# Battery_power.net
KiCad netlist of a schematic drawn in Altium Designer
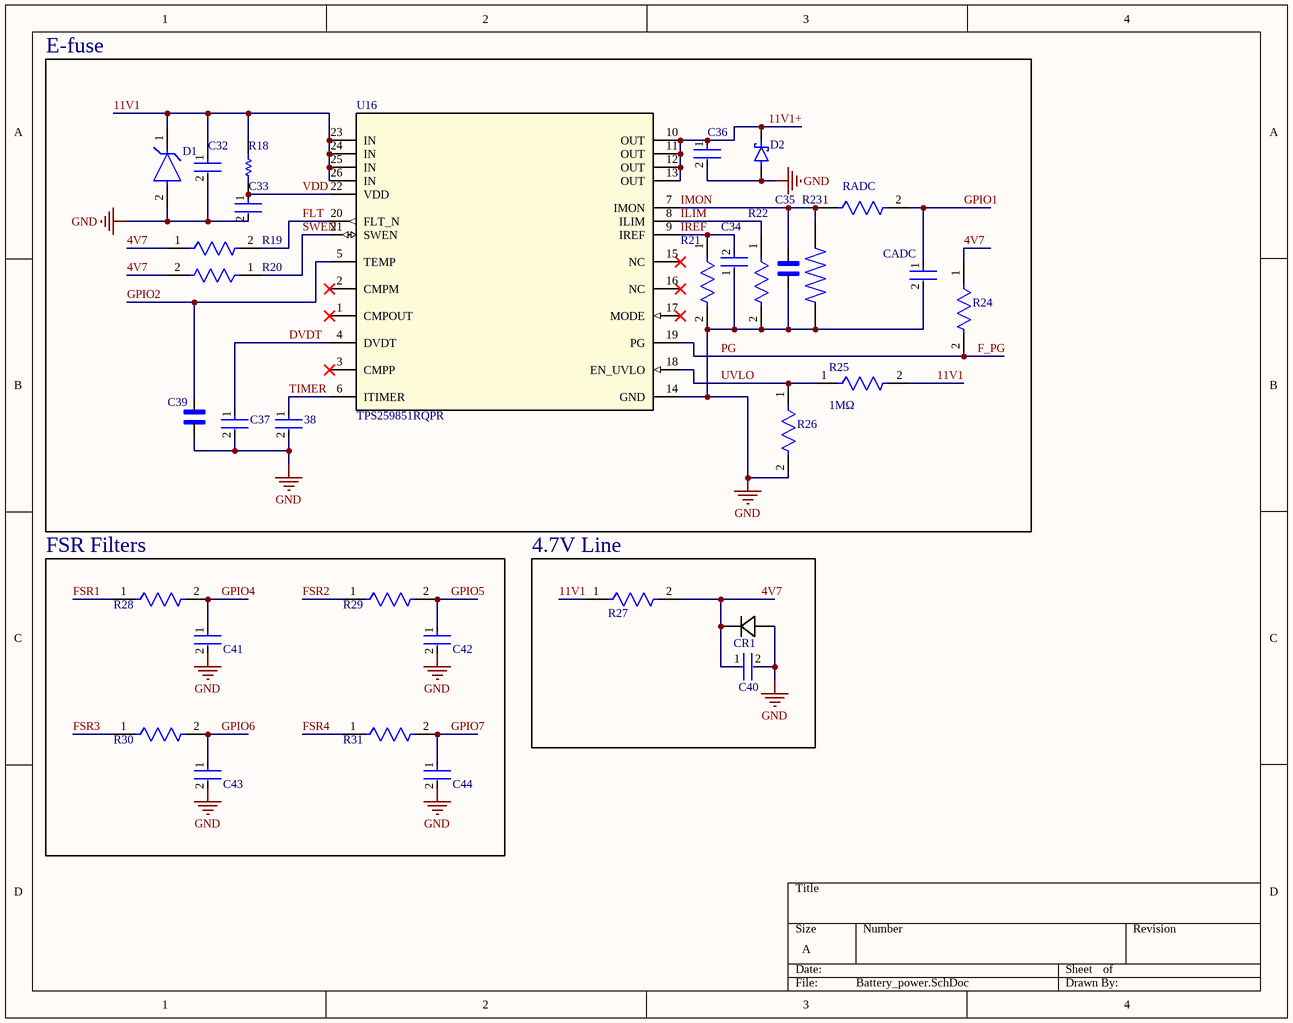
[diagram p0: Battery_power.SchDoc]

(export (version "E")
  (design (tool "Eeschema 10.0.6"))
  (components
    (comp (ref "38")
      (value "GRM155R71H104KE14D")
      (footprint "FP-GRM155-0_05-IPC_B")
      (description "Chip Multilayer Ceramic Capacitors for General Purpose, 0402, 0.10uF, X7R, 15%, 10%, 50V")
      (fields (field (name "VOLTAGE") "50V") (field (name "TOLERANCE") "10%"))
      (libsource (lib "Altium Content Vault") (part "02cd4be3c70576c341d710602a673aa"))
    )
    (comp (ref "C32")
      (value "CC0805KRX7R9BB104")
      (footprint "FP-CC0805-0_85-MFG")
      (description "CAP CER 0.1UF 50V X7R 0805")
      (fields (field (name "TOLERANCE") "0.1") (field (name "MANUFACTURER") "Yageo"))
      (libsource (lib "Altium Content Vault") (part "11868f565c42a9108669ba33697ecf6"))
    )
    (comp (ref "C33")
      (value "CC0805KKX7R9BB225")
      (footprint "FP-CC0805-0_85-MFG")
      (description "CAP CER 2.2UF 50V X7R 0805")
      (fields
        (field (name "OCTOPART") "https://octopart.com/cc0805kkx7r9bb225-yageo-51849248")
        (field (name "TOLERANCE") "0.1")
      )
      (libsource (lib "Altium Content Vault") (part "11868f565c42a9108669ba33697ecf6"))
    )
    (comp (ref "C34")
      (value "C1608C0G1E472J080AA")
      (footprint "FP-C1608-080-0_1-IPC_A")
      (description "Multilayer Ceramic Capacitors 4.7nF ±5% 25V C0G SMD 0603")
      (fields (field (name "TOLERANCE") "5%"))
      (libsource (lib "Altium Content Vault") (part "236180d848d6139a670b325ea6854c9"))
    )
    (comp (ref "C35")
      (value "GRM1885C1H101JA01D")
      (footprint "CAPC1608X90N")
      (description "SMD Capacitor C0G(EIA) with Capacitance: 100pF Tol. 5%. Rated Voltage: 50Vdc")
      (fields (field (name "MF") "Murata Electronics"))
      (libsource (lib "Bryan Heddle") (part "GRM1885C1H101JA01D"))
    )
    (comp (ref "C36")
      (value "CC0805KKX7R9BB225")
      (footprint "FP-CC0805-0_85-MFG")
      (description "CAP CER 2.2UF 50V X7R 0805")
      (fields
        (field (name "OCTOPART") "https://octopart.com/cc0805kkx7r9bb225-yageo-51849248")
        (field (name "TOLERANCE") "0.1")
      )
      (libsource (lib "Altium Content Vault") (part "11868f565c42a9108669ba33697ecf6"))
    )
    (comp (ref "C37")
      (value "GRM155R71H104KE14D")
      (footprint "FP-GRM155-0_05-IPC_B")
      (description "Chip Multilayer Ceramic Capacitors for General Purpose, 0402, 0.10uF, X7R, 15%, 10%, 50V")
      (fields (field (name "VOLTAGE") "50V") (field (name "TOLERANCE") "10%"))
      (libsource (lib "Altium Content Vault") (part "02cd4be3c70576c341d710602a673aa"))
    )
    (comp (ref "C39")
      (value "GRM1885C1H101JA01D")
      (footprint "CAPC1608X90N")
      (description "SMD Capacitor C0G(EIA) with Capacitance: 100pF Tol. 5%. Rated Voltage: 50Vdc")
      (fields (field (name "MF") "Murata Electronics"))
      (libsource (lib "Bryan Heddle") (part "GRM1885C1H101JA01D"))
    )
    (comp (ref "C40")
      (value "GRM155R71H104KE14D")
      (footprint "FP-GRM155-0_05-IPC_B")
      (description "Chip Multilayer Ceramic Capacitors for General Purpose, 0402, 0.10uF, X7R, 15%, 10%, 50V")
      (fields (field (name "VOLTAGE") "50V") (field (name "TOLERANCE") "10%"))
      (libsource (lib "Altium Content Vault") (part "02cd4be3c70576c341d710602a673aa"))
    )
    (comp (ref "C41")
      (value "GRM155R71H104KE14D")
      (footprint "FP-GRM155-0_05-IPC_B")
      (description "Chip Multilayer Ceramic Capacitors for General Purpose, 0402, 0.10uF, X7R, 15%, 10%, 50V")
      (fields (field (name "VOLTAGE") "50V") (field (name "TOLERANCE") "10%"))
      (libsource (lib "Altium Content Vault") (part "02cd4be3c70576c341d710602a673aa"))
    )
    (comp (ref "C42")
      (value "GRM155R71H104KE14D")
      (footprint "FP-GRM155-0_05-IPC_B")
      (description "Chip Multilayer Ceramic Capacitors for General Purpose, 0402, 0.10uF, X7R, 15%, 10%, 50V")
      (fields (field (name "VOLTAGE") "50V") (field (name "TOLERANCE") "10%"))
      (libsource (lib "Altium Content Vault") (part "02cd4be3c70576c341d710602a673aa"))
    )
    (comp (ref "C43")
      (value "GRM155R71H104KE14D")
      (footprint "FP-GRM155-0_05-IPC_B")
      (description "Chip Multilayer Ceramic Capacitors for General Purpose, 0402, 0.10uF, X7R, 15%, 10%, 50V")
      (fields (field (name "VOLTAGE") "50V") (field (name "TOLERANCE") "10%"))
      (libsource (lib "Altium Content Vault") (part "02cd4be3c70576c341d710602a673aa"))
    )
    (comp (ref "C44")
      (value "GRM155R71H104KE14D")
      (footprint "FP-GRM155-0_05-IPC_B")
      (description "Chip Multilayer Ceramic Capacitors for General Purpose, 0402, 0.10uF, X7R, 15%, 10%, 50V")
      (fields (field (name "VOLTAGE") "50V") (field (name "TOLERANCE") "10%"))
      (libsource (lib "Altium Content Vault") (part "02cd4be3c70576c341d710602a673aa"))
    )
    (comp (ref "CADC")
      (value "CGA4C2C0G1H822J060AA")
      (footprint "FP-CGA4J-IPC_A")
      (description "Cap Ceramic 8.2nF 50V C0G 5% Pad SMD 0805 +125°C Automotive T/R")
      (fields (field (name "TOLERANCE") "5%"))
      (libsource (lib "Altium Content Vault") (part "b4654b650e69147ec39a6b967a45e02"))
    )
    (comp (ref "CR1")
      (value "BZT52C4V7-7-F")
      (footprint "SOD123_DIO")
      (description "No Description Available")
      (fields (field (name "COPYRIGHT") "Copyright (C) 2026 Ultra Librarian. All rights reserved."))
      (libsource (lib "BZT52C4V7-7-F") (part "BZT52C4V7-7-F"))
    )
    (comp (ref "D1")
      (value "SMBJ12A")
      (footprint "FP-SMBJ-MFG")
      (description "TVS DIODE 12V 19.9V DO214AA")
      (fields
        (field (name "OCTOPART") "https://octopart.com/smbj12a-littelfuse-28708")
        (field (name "MANUFACTURER") "Littelfuse")
      )
      (libsource (lib "Altium Content Vault") (part "f813f71cba58e380607f5dd3caf9714"))
    )
    (comp (ref "D2")
      (value "PDS1040-13")
      (footprint "DIO_PDS1040-13")
      (description "Diode Schottky 40V 10A 3Pin PowerDI 5")
      (fields (field (name "MF") "Diodes Inc."))
      (libsource (lib "Bryan Heddle") (part "PDS1040-13"))
    )
    (comp (ref "R18")
      (value "CRCW040210R0FKED")
      (footprint "RESC1005X40X25NL05T05")
      (fields (field (name "MANUFACTURER") "Vishay Dale"))
      (libsource (lib "Altium Content Vault") (part "RES"))
    )
    (comp (ref "R19")
      (value "CRCW040210K0FKEDC")
      (footprint "FP-CRCW0402-C-e3-IPC_C")
      (description "RES 10K OHM 1% 1/16W 0402")
      (fields (field (name "TOLERANCE") "1%"))
      (libsource (lib "Altium Content Vault") (part "1029c3af85768c4190bb7ad29bc67b5"))
    )
    (comp (ref "R20")
      (value "CRCW0402100KFKED")
      (footprint "FP-CRCW0402-e3-IPC_C")
      (description "RES Thick Film, 100kΩ, 1%, 0.063W, 100ppm/°C, 0402")
      (fields (field (name "TOLERANCE") "1%"))
      (libsource (lib "Altium Content Vault") (part "1029c3af85768c4190bb7ad29bc67b5"))
    )
    (comp (ref "R21")
      (value "RT0402BRD0748K7L")
      (footprint "FP-RT0402-MFG")
      (description "RES SMD 48.7K OHM 0.1% 1/16W")
      (fields
        (field (name "OCTOPART") "https://octopart.com/rt0402brd0748k7l-yageo-1374792")
        (field (name "MANUFACTURER") "Yageo")
      )
      (libsource (lib "Altium Content Vault") (part "1029c3af85768c4190bb7ad29bc67b5"))
    )
    (comp (ref "R22")
      (value "RC0402FR-07499RL")
      (footprint "FP-RC0402-0_4-IPC_A")
      (description "RES 499 OHM 1% 1/16W 0402")
      (fields (field (name "TOLERANCE") "1%"))
      (libsource (lib "Altium Content Vault") (part "1029c3af85768c4190bb7ad29bc67b5"))
    )
    (comp (ref "R23")
      (value "ERA3AEB102V")
      (footprint "RES_ERA3AEB102V")
      (description "Resistor, SMD 1 kOhm 0603 0.1 %")
      (fields (field (name "DIGI-KEY_PART_NUMBER") "P1.0KDBCT-ND") (field (name "MP") "ERA-3AEB102V"))
      (libsource (lib "Bryan Heddle") (part "ERA3AEB102V"))
    )
    (comp (ref "R24")
      (value "CRCW040210K0FKEDC")
      (footprint "FP-CRCW0402-C-e3-IPC_C")
      (description "RES 10K OHM 1% 1/16W 0402")
      (fields (field (name "TOLERANCE") "1%"))
      (libsource (lib "Altium Content Vault") (part "1029c3af85768c4190bb7ad29bc67b5"))
    )
    (comp (ref "R25")
      (value "CRCW04021M00FKED")
      (footprint "CRCW0402-e3_MFG")
      (description "63mW Thick Film Resistors 75V ±1% ±100ppm/℃ 1MΩ 0402 Chip Resistor - Surface Mount ROHS")
      (fields (field (name "TOLERANCE") "1%"))
      (libsource (lib "Altium Content Vault") (part "beb0a2e81d78bb8429d162089e89c6a"))
    )
    (comp (ref "R26")
      (value "CRCW0402121KFKED")
      (footprint "FP-CRCW0402-e3-MFG")
      (description "RES Thick Film, 121kΩ, 1%, 0.063W, 100ppm/°C, 0402")
      (fields (field (name "TOLERANCE") "1%"))
      (libsource (lib "Altium Content Vault") (part "1029c3af85768c4190bb7ad29bc67b5"))
    )
    (comp (ref "R27")
      (value "RC0603FR-0710KL")
      (footprint "FP-RC0603-0_55-IPC_C")
      (description "RES 10K OHM 1% 1/10W 0603")
      (fields (field (name "TOLERANCE") "1%"))
      (libsource (lib "Altium Content Vault") (part "1029c3af85768c4190bb7ad29bc67b5"))
    )
    (comp (ref "R28")
      (value "CRCW08054K70FKEA")
      (footprint "FP-CRCW0805-e3-IPC_B")
      (description "RES Thick Film, 4.7kΩ, 1%, 0.125W, 100ppm/°C, 0805")
      (fields (field (name "TOLERANCE") "1%"))
      (libsource (lib "Altium Content Vault") (part "1029c3af85768c4190bb7ad29bc67b5"))
    )
    (comp (ref "R29")
      (value "CRCW08054K70FKEA")
      (footprint "FP-CRCW0805-e3-IPC_B")
      (description "RES Thick Film, 4.7kΩ, 1%, 0.125W, 100ppm/°C, 0805")
      (fields (field (name "TOLERANCE") "1%"))
      (libsource (lib "Altium Content Vault") (part "1029c3af85768c4190bb7ad29bc67b5"))
    )
    (comp (ref "R30")
      (value "CRCW08054K70FKEA")
      (footprint "FP-CRCW0805-e3-IPC_B")
      (description "RES Thick Film, 4.7kΩ, 1%, 0.125W, 100ppm/°C, 0805")
      (fields (field (name "TOLERANCE") "1%"))
      (libsource (lib "Altium Content Vault") (part "1029c3af85768c4190bb7ad29bc67b5"))
    )
    (comp (ref "R31")
      (value "CRCW08054K70FKEA")
      (footprint "FP-CRCW0805-e3-IPC_B")
      (description "RES Thick Film, 4.7kΩ, 1%, 0.125W, 100ppm/°C, 0805")
      (fields (field (name "TOLERANCE") "1%"))
      (libsource (lib "Altium Content Vault") (part "1029c3af85768c4190bb7ad29bc67b5"))
    )
    (comp (ref "RADC")
      (value "CRCW08054K70FKEA")
      (footprint "FP-CRCW0805-e3-IPC_B")
      (description "RES Thick Film, 4.7kΩ, 1%, 0.125W, 100ppm/°C, 0805")
      (fields (field (name "TOLERANCE") "1%"))
      (libsource (lib "Altium Content Vault") (part "1029c3af85768c4190bb7ad29bc67b5"))
    )
    (comp (ref "U16")
      (value "TPS259851RQPR")
      (footprint "RQP0026A-MFG")
      (fields (field (name "COPYRIGHT") "Copyright (C) 2025 Ultra Librarian. All rights reserved."))
      (libsource (lib "Bryan Heddle") (part "TPS259851RQPR"))
    )
  )
  (nets
    (net (code "1") (name "/4V7") (class "Default")
      (node (ref "C40") (pin "1") (pinfunction "1_1") (pintype "passive"))
      (node (ref "CR1") (pin "1") (pinfunction "1_1") (pintype "passive"))
      (node (ref "R19") (pin "1") (pinfunction "1_1") (pintype "passive"))
      (node (ref "R20") (pin "2") (pinfunction "2_2") (pintype "passive"))
      (node (ref "R24") (pin "1") (pinfunction "1_1") (pintype "passive"))
      (node (ref "R27") (pin "2") (pinfunction "2_2") (pintype "passive"))
    )
    (net (code "2") (name "/11V1") (class "Default")
      (node (ref "C32") (pin "1") (pinfunction "1_1") (pintype "passive"))
      (node (ref "D1") (pin "1") (pinfunction "C_1") (pintype "passive"))
      (node (ref "R18") (pin "1") (pinfunction "1_1") (pintype "passive"))
      (node (ref "R25") (pin "2") (pinfunction "2_2") (pintype "passive"))
      (node (ref "R27") (pin "1") (pinfunction "1_1") (pintype "passive"))
      (node (ref "U16") (pin "23") (pinfunction "IN_23") (pintype "power_in"))
      (node (ref "U16") (pin "24") (pinfunction "IN_24") (pintype "power_in"))
      (node (ref "U16") (pin "25") (pinfunction "IN_25") (pintype "power_in"))
      (node (ref "U16") (pin "26") (pinfunction "IN_26") (pintype "power_in"))
    )
    (net (code "3") (name "/11V1+") (class "Default")
      (node (ref "C36") (pin "1") (pinfunction "1_1") (pintype "passive"))
      (node (ref "D2") (pin "3") (pinfunction "K_3") (pintype "passive"))
      (node (ref "U16") (pin "10") (pinfunction "OUT_10") (pintype "power_in"))
      (node (ref "U16") (pin "11") (pinfunction "OUT_11") (pintype "power_in"))
      (node (ref "U16") (pin "12") (pinfunction "OUT_12") (pintype "power_in"))
      (node (ref "U16") (pin "13") (pinfunction "OUT_13") (pintype "power_in"))
    )
    (net (code "4") (name "/DVDT") (class "Default")
      (node (ref "C37") (pin "1") (pinfunction "1_1") (pintype "passive"))
      (node (ref "U16") (pin "4") (pinfunction "DVDT_4") (pintype "passive"))
    )
    (net (code "5") (name "/FLT") (class "Default")
      (node (ref "R19") (pin "2") (pinfunction "2_2") (pintype "passive"))
      (node (ref "U16") (pin "20") (pinfunction "FLT_N_20") (pintype "output"))
    )
    (net (code "6") (name "/FSR1") (class "Default")
      (node (ref "R28") (pin "1") (pinfunction "1_1") (pintype "passive"))
    )
    (net (code "7") (name "/FSR2") (class "Default")
      (node (ref "R29") (pin "1") (pinfunction "1_1") (pintype "passive"))
    )
    (net (code "8") (name "/FSR3") (class "Default")
      (node (ref "R30") (pin "1") (pinfunction "1_1") (pintype "passive"))
    )
    (net (code "9") (name "/FSR4") (class "Default")
      (node (ref "R31") (pin "1") (pinfunction "1_1") (pintype "passive"))
    )
    (net (code "10") (name "/F_PG") (class "Default")
      (node (ref "R24") (pin "2") (pinfunction "2_2") (pintype "passive"))
      (node (ref "U16") (pin "19") (pinfunction "PG_19") (pintype "open_collector"))
    )
    (net (code "11") (name "/GPIO1") (class "Default")
      (node (ref "CADC") (pin "1") (pinfunction "1_1") (pintype "passive"))
      (node (ref "RADC") (pin "2") (pinfunction "2_2") (pintype "passive"))
    )
    (net (code "12") (name "/GPIO2") (class "Default")
      (node (ref "C39") (pin "2") (pinfunction "2_2") (pintype "passive"))
      (node (ref "U16") (pin "5") (pinfunction "TEMP_5") (pintype "passive"))
    )
    (net (code "13") (name "/GPIO4") (class "Default")
      (node (ref "C41") (pin "1") (pinfunction "1_1") (pintype "passive"))
      (node (ref "R28") (pin "2") (pinfunction "2_2") (pintype "passive"))
    )
    (net (code "14") (name "/GPIO5") (class "Default")
      (node (ref "C42") (pin "1") (pinfunction "1_1") (pintype "passive"))
      (node (ref "R29") (pin "2") (pinfunction "2_2") (pintype "passive"))
    )
    (net (code "15") (name "/GPIO6") (class "Default")
      (node (ref "C43") (pin "1") (pinfunction "1_1") (pintype "passive"))
      (node (ref "R30") (pin "2") (pinfunction "2_2") (pintype "passive"))
    )
    (net (code "16") (name "/GPIO7") (class "Default")
      (node (ref "C44") (pin "1") (pinfunction "1_1") (pintype "passive"))
      (node (ref "R31") (pin "2") (pinfunction "2_2") (pintype "passive"))
    )
    (net (code "17") (name "/ILIM") (class "Default")
      (node (ref "R22") (pin "1") (pinfunction "1_1") (pintype "passive"))
      (node (ref "U16") (pin "8") (pinfunction "ILIM_8") (pintype "passive"))
    )
    (net (code "18") (name "/IMON") (class "Default")
      (node (ref "C35") (pin "2") (pinfunction "2_2") (pintype "passive"))
      (node (ref "R23") (pin "2") (pinfunction "2_2") (pintype "passive"))
      (node (ref "RADC") (pin "1") (pinfunction "1_1") (pintype "passive"))
      (node (ref "U16") (pin "7") (pinfunction "IMON_7") (pintype "passive"))
    )
    (net (code "19") (name "/IREF") (class "Default")
      (node (ref "C34") (pin "2") (pinfunction "2_2") (pintype "passive"))
      (node (ref "R21") (pin "1") (pinfunction "1_1") (pintype "passive"))
      (node (ref "U16") (pin "9") (pinfunction "IREF_9") (pintype "passive"))
    )
    (net (code "20") (name "/SWEN") (class "Default")
      (node (ref "R20") (pin "1") (pinfunction "1_1") (pintype "passive"))
      (node (ref "U16") (pin "21") (pinfunction "SWEN_21") (pintype "bidirectional"))
    )
    (net (code "21") (name "/TIMER") (class "Default")
      (node (ref "38") (pin "1") (pinfunction "1_1") (pintype "passive"))
      (node (ref "U16") (pin "6") (pinfunction "ITIMER_6") (pintype "passive"))
    )
    (net (code "22") (name "/UVLO") (class "Default")
      (node (ref "R25") (pin "1") (pinfunction "1_1") (pintype "passive"))
      (node (ref "R26") (pin "1") (pinfunction "1_1") (pintype "passive"))
      (node (ref "U16") (pin "18") (pinfunction "EN_UVLO_18") (pintype "input"))
    )
    (net (code "23") (name "/VDD") (class "Default")
      (node (ref "C33") (pin "1") (pinfunction "1_1") (pintype "passive"))
      (node (ref "R18") (pin "2") (pinfunction "2_2") (pintype "passive"))
      (node (ref "U16") (pin "22") (pinfunction "VDD_22") (pintype "power_in"))
    )
    (net (code "24") (name "GND") (class "Default")
      (node (ref "38") (pin "2") (pinfunction "2_2") (pintype "passive"))
      (node (ref "C32") (pin "2") (pinfunction "2_2") (pintype "passive"))
      (node (ref "C33") (pin "2") (pinfunction "2_2") (pintype "passive"))
      (node (ref "C34") (pin "1") (pinfunction "1_1") (pintype "passive"))
      (node (ref "C35") (pin "1") (pinfunction "1_1") (pintype "passive"))
      (node (ref "C36") (pin "2") (pinfunction "2_2") (pintype "passive"))
      (node (ref "C37") (pin "2") (pinfunction "2_2") (pintype "passive"))
      (node (ref "C39") (pin "1") (pinfunction "1_1") (pintype "passive"))
      (node (ref "C40") (pin "2") (pinfunction "2_2") (pintype "passive"))
      (node (ref "C41") (pin "2") (pinfunction "2_2") (pintype "passive"))
      (node (ref "C42") (pin "2") (pinfunction "2_2") (pintype "passive"))
      (node (ref "C43") (pin "2") (pinfunction "2_2") (pintype "passive"))
      (node (ref "C44") (pin "2") (pinfunction "2_2") (pintype "passive"))
      (node (ref "CADC") (pin "2") (pinfunction "2_2") (pintype "passive"))
      (node (ref "CR1") (pin "2") (pinfunction "2_2") (pintype "passive"))
      (node (ref "D1") (pin "2") (pinfunction "A_2") (pintype "passive"))
      (node (ref "D2") (pin "1") (pinfunction "A_1") (pintype "passive"))
      (node (ref "D2") (pin "2") (pinfunction "A__1_2") (pintype "passive"))
      (node (ref "R21") (pin "2") (pinfunction "2_2") (pintype "passive"))
      (node (ref "R22") (pin "2") (pinfunction "2_2") (pintype "passive"))
      (node (ref "R23") (pin "1") (pinfunction "1_1") (pintype "passive"))
      (node (ref "R26") (pin "2") (pinfunction "2_2") (pintype "passive"))
      (node (ref "U16") (pin "14") (pinfunction "GND_14") (pintype "power_in"))
    )
    (net (code "25") (name "unconnected-(U16-CMPM-Pad2)") (class "Default")
      (node (ref "U16") (pin "2") (pinfunction "CMPM_2") (pintype "passive+no_connect"))
    )
    (net (code "26") (name "unconnected-(U16-CMPOUT-Pad1)") (class "Default")
      (node (ref "U16") (pin "1") (pinfunction "CMPOUT_1") (pintype "passive+no_connect"))
    )
    (net (code "27") (name "unconnected-(U16-CMPP-Pad3)") (class "Default")
      (node (ref "U16") (pin "3") (pinfunction "CMPP_3") (pintype "passive+no_connect"))
    )
    (net (code "28") (name "unconnected-(U16-MODE-Pad17)") (class "Default")
      (node (ref "U16") (pin "17") (pinfunction "MODE_17") (pintype "input+no_connect"))
    )
    (net (code "29") (name "unconnected-(U16-NC-Pad15)") (class "Default")
      (node (ref "U16") (pin "15") (pinfunction "NC_15") (pintype "passive+no_connect"))
    )
    (net (code "30") (name "unconnected-(U16-NC-Pad16)") (class "Default")
      (node (ref "U16") (pin "16") (pinfunction "NC_16") (pintype "passive+no_connect"))
    )
  )
)
